# DSI_FLAT.net
KiCad netlist of a schematic drawn in Altium Designer
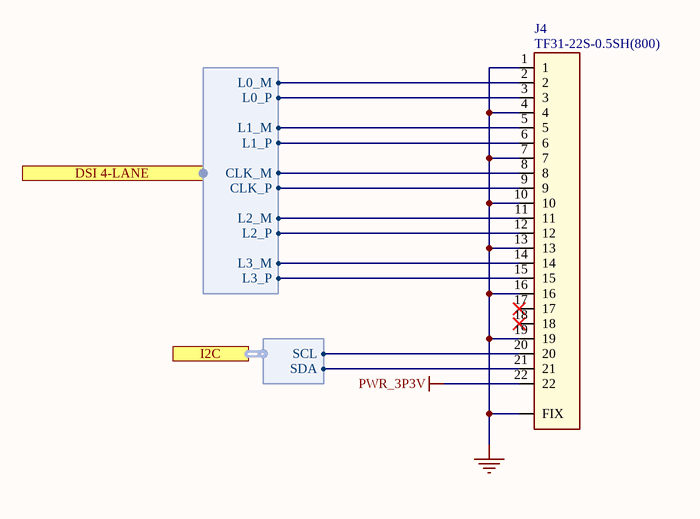
[diagram p0: DSI_FLAT.SchDoc]

(export (version "E")
  (design (tool "Eeschema 10.0.6"))
  (components
    (comp (ref "J4")
      (value "TF31-22S-0.5SH(800)")
      (footprint "TF31-22S-0.5SH(800)")
      (description "CONN FFC/FPC Connector, 22 Contact(s), 1 Row(s), BOTTOM CONTACT, Female, Right Angle, 0.5mm Pitch")
      (fields (field (name "MANUFACTURER") "Hirose"))
      (libsource (lib "Clean") (part "TF31-22S-0.5SH(800)"))
    )
  )
  (nets
    (net (code "3") (name "/CLK_M") (class "Default")
      (node (ref "J4") (pin "8") (pinfunction "8_8") (pintype "passive"))
    )
    (net (code "4") (name "/CLK_P") (class "Default")
      (node (ref "J4") (pin "9") (pinfunction "9_9") (pintype "passive"))
    )
    (net (code "5") (name "/L0_M") (class "Default")
      (node (ref "J4") (pin "2") (pinfunction "2_2") (pintype "passive"))
    )
    (net (code "6") (name "/L0_P") (class "Default")
      (node (ref "J4") (pin "3") (pinfunction "3_3") (pintype "passive"))
    )
    (net (code "7") (name "/L1_M") (class "Default")
      (node (ref "J4") (pin "5") (pinfunction "5_5") (pintype "passive"))
    )
    (net (code "8") (name "/L1_P") (class "Default")
      (node (ref "J4") (pin "6") (pinfunction "6_6") (pintype "passive"))
    )
    (net (code "9") (name "/L2_M") (class "Default")
      (node (ref "J4") (pin "11") (pinfunction "11_11") (pintype "passive"))
    )
    (net (code "10") (name "/L2_P") (class "Default")
      (node (ref "J4") (pin "12") (pinfunction "12_12") (pintype "passive"))
    )
    (net (code "11") (name "/L3_M") (class "Default")
      (node (ref "J4") (pin "14") (pinfunction "14_14") (pintype "passive"))
    )
    (net (code "12") (name "/L3_P") (class "Default")
      (node (ref "J4") (pin "15") (pinfunction "15_15") (pintype "passive"))
    )
    (net (code "13") (name "/SCL") (class "Default")
      (node (ref "J4") (pin "20") (pinfunction "20_20") (pintype "passive"))
    )
    (net (code "14") (name "/SDA") (class "Default")
      (node (ref "J4") (pin "21") (pinfunction "21_21") (pintype "passive"))
    )
    (net (code "17") (name "GND") (class "Default")
      (node (ref "J4") (pin "1") (pinfunction "1_1") (pintype "passive"))
      (node (ref "J4") (pin "10") (pinfunction "10_10") (pintype "passive"))
      (node (ref "J4") (pin "13") (pinfunction "13_13") (pintype "passive"))
      (node (ref "J4") (pin "16") (pinfunction "16_16") (pintype "passive"))
      (node (ref "J4") (pin "19") (pinfunction "19_19") (pintype "passive"))
      (node (ref "J4") (pin "4") (pinfunction "4_4") (pintype "passive"))
      (node (ref "J4") (pin "7") (pinfunction "7_7") (pintype "passive"))
      (node (ref "J4") (pin "FIX") (pinfunction "FIX_FIX") (pintype "passive"))
    )
    (net (code "18") (name "PWR_3P3V") (class "Default")
      (node (ref "J4") (pin "22") (pinfunction "22_22") (pintype "passive"))
    )
    (net (code "19") (name "unconnected-(J4-Pad17)") (class "Default")
      (node (ref "J4") (pin "17") (pinfunction "17_17") (pintype "passive+no_connect"))
    )
    (net (code "20") (name "unconnected-(J4-Pad18)") (class "Default")
      (node (ref "J4") (pin "18") (pinfunction "18_18") (pintype "passive+no_connect"))
    )
  )
)
